# UserInterface.net
KiCad netlist of a schematic drawn in Altium Designer
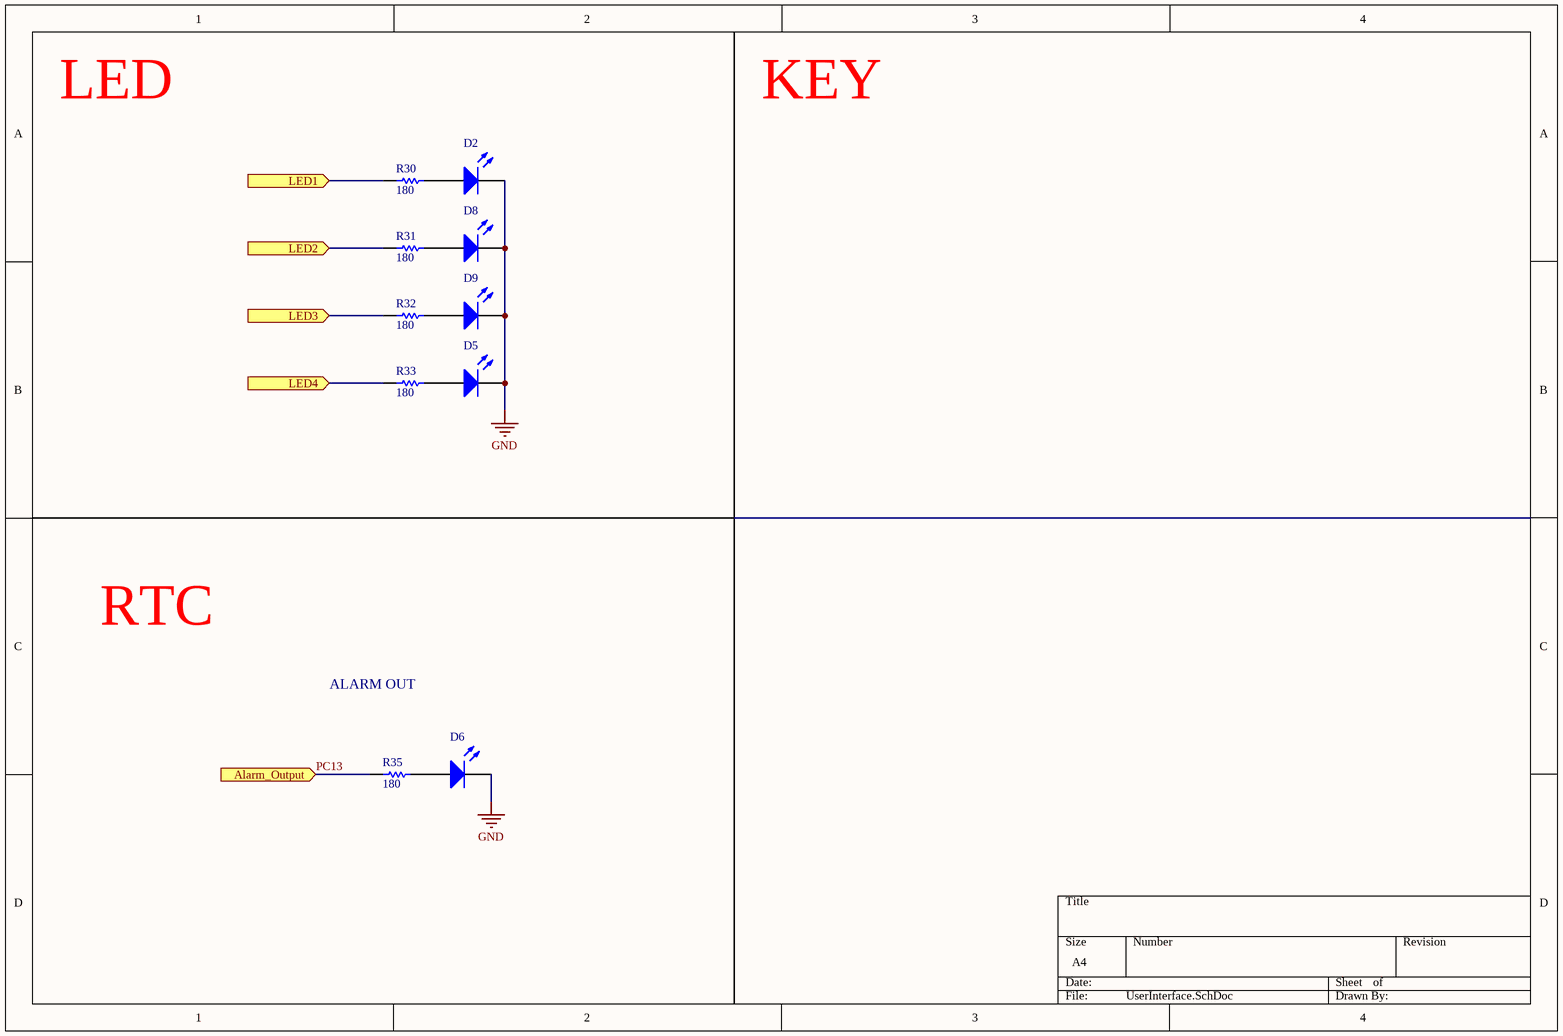
[diagram p0: UserInterface.SchDoc]

(export (version "E")
  (design (tool "Eeschema 10.0.6"))
  (components
    (comp (ref "D2")
      (value "LED3")
      (footprint "LED-1206")
      (description "Typical BLUE SiC LED")
      (fields (field (name "PUBLISHER") "Altium Limited"))
      (libsource (lib "Miscellaneous Devices") (part "LED3"))
    )
    (comp (ref "D5")
      (value "LED3")
      (footprint "LED-1206")
      (description "Typical BLUE SiC LED")
      (fields (field (name "PUBLISHER") "Altium Limited"))
      (libsource (lib "Miscellaneous Devices") (part "LED3"))
    )
    (comp (ref "D6")
      (value "LED3")
      (footprint "LED-1206")
      (description "Typical BLUE SiC LED")
      (fields (field (name "PUBLISHER") "Altium Limited"))
      (libsource (lib "Miscellaneous Devices") (part "LED3"))
    )
    (comp (ref "D8")
      (value "LED3")
      (footprint "LED-1206")
      (description "Typical BLUE SiC LED")
      (fields (field (name "PUBLISHER") "Altium Limited"))
      (libsource (lib "Miscellaneous Devices") (part "LED3"))
    )
    (comp (ref "D9")
      (value "LED3")
      (footprint "LED-1206")
      (description "Typical BLUE SiC LED")
      (fields (field (name "PUBLISHER") "Altium Limited"))
      (libsource (lib "Miscellaneous Devices") (part "LED3"))
    )
    (comp (ref "R30")
      (value "180")
      (description "Semiconductor Resistor")
      (fields (field (name "PUBLISHER") "Altium Limited"))
      (libsource (lib "Miscellaneous Devices") (part "Res Semi"))
    )
    (comp (ref "R31")
      (value "180")
      (description "Semiconductor Resistor")
      (fields (field (name "PUBLISHER") "Altium Limited"))
      (libsource (lib "Miscellaneous Devices") (part "Res Semi"))
    )
    (comp (ref "R32")
      (value "180")
      (description "Semiconductor Resistor")
      (fields (field (name "PUBLISHER") "Altium Limited"))
      (libsource (lib "Miscellaneous Devices") (part "Res Semi"))
    )
    (comp (ref "R33")
      (value "180")
      (description "Semiconductor Resistor")
      (fields (field (name "PUBLISHER") "Altium Limited"))
      (libsource (lib "Miscellaneous Devices") (part "Res Semi"))
    )
    (comp (ref "R35")
      (value "180")
      (description "Semiconductor Resistor")
      (fields (field (name "PUBLISHER") "Altium Limited"))
      (libsource (lib "Miscellaneous Devices") (part "Res Semi"))
    )
  )
  (nets
    (net (code "1") (name "/LED1") (class "Default")
      (node (ref "R30") (pin "1") (pinfunction "1_1") (pintype "passive"))
    )
    (net (code "2") (name "/LED2") (class "Default")
      (node (ref "R31") (pin "1") (pinfunction "1_1") (pintype "passive"))
    )
    (net (code "3") (name "/LED3") (class "Default")
      (node (ref "R32") (pin "1") (pinfunction "1_1") (pintype "passive"))
    )
    (net (code "4") (name "/LED4") (class "Default")
      (node (ref "R33") (pin "1") (pinfunction "1_1") (pintype "passive"))
    )
    (net (code "5") (name "/PC13") (class "Default")
      (node (ref "R35") (pin "1") (pinfunction "1_1") (pintype "passive"))
    )
    (net (code "6") (name "GND") (class "Default")
      (node (ref "D2") (pin "2") (pinfunction "K_2") (pintype "passive"))
      (node (ref "D5") (pin "2") (pinfunction "K_2") (pintype "passive"))
      (node (ref "D6") (pin "2") (pinfunction "K_2") (pintype "passive"))
      (node (ref "D8") (pin "2") (pinfunction "K_2") (pintype "passive"))
      (node (ref "D9") (pin "2") (pinfunction "K_2") (pintype "passive"))
    )
    (net (code "7") (name "Net-(D2-A)") (class "Default")
      (node (ref "D2") (pin "1") (pinfunction "A_1") (pintype "passive"))
      (node (ref "R30") (pin "2") (pinfunction "2_2") (pintype "passive"))
    )
    (net (code "8") (name "Net-(D5-A)") (class "Default")
      (node (ref "D5") (pin "1") (pinfunction "A_1") (pintype "passive"))
      (node (ref "R33") (pin "2") (pinfunction "2_2") (pintype "passive"))
    )
    (net (code "9") (name "Net-(D6-A)") (class "Default")
      (node (ref "D6") (pin "1") (pinfunction "A_1") (pintype "passive"))
      (node (ref "R35") (pin "2") (pinfunction "2_2") (pintype "passive"))
    )
    (net (code "10") (name "Net-(D8-A)") (class "Default")
      (node (ref "D8") (pin "1") (pinfunction "A_1") (pintype "passive"))
      (node (ref "R31") (pin "2") (pinfunction "2_2") (pintype "passive"))
    )
    (net (code "11") (name "Net-(D9-A)") (class "Default")
      (node (ref "D9") (pin "1") (pinfunction "A_1") (pintype "passive"))
      (node (ref "R32") (pin "2") (pinfunction "2_2") (pintype "passive"))
    )
  )
)
